# LCM32F037H6S8_024VDC_SCH_V1_0.net
KiCad netlist of a schematic drawn in Altium Designer
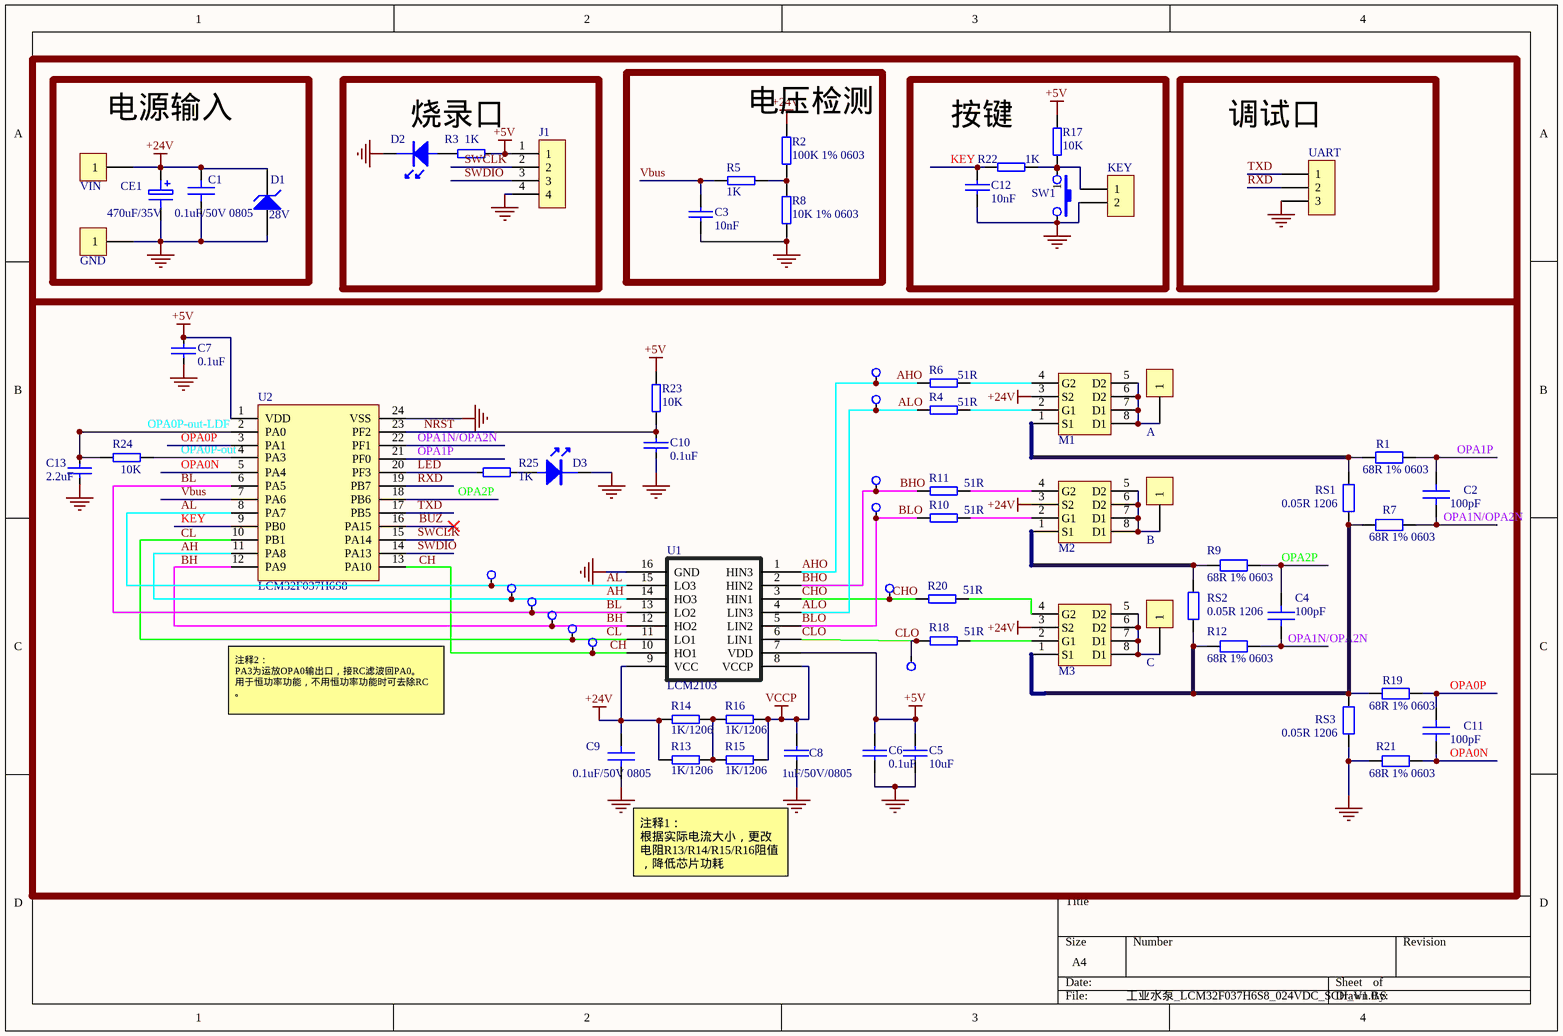
[diagram p0: 工业水泵_LCM32F037H6S8_024VDC_SCH_V1.0.SchDoc]

(export (version "E")
  (design (tool "Eeschema 10.0.6"))
  (components
    (comp (ref "A")
      (value "CON1")
      (footprint "CON-F1.5")
      (description "Connector")
      (libsource (lib "") (part "CON1_2"))
    )
    (comp (ref "B")
      (value "CON1")
      (footprint "CON-F1.5")
      (description "Connector")
      (libsource (lib "Miscellaneous Devices-HK") (part "CON1"))
    )
    (comp (ref "C")
      (value "CON1")
      (footprint "CON-F1.5")
      (description "Connector")
      (libsource (lib "") (part "CON1_2"))
    )
    (comp (ref "C1")
      (value "0.1uF/50V 0805")
      (footprint "C0805")
      (description "贴片电容")
      (libsource (lib "SCH-Tineco") (part "C-0603-104K50-X7R"))
    )
    (comp (ref "C2")
      (value "100pF")
      (footprint "C0603")
      (description "贴片电容")
      (libsource (lib "SCH-Tineco") (part "C-0603-104K50-X7R"))
    )
    (comp (ref "C3")
      (value "10nF")
      (footprint "C0603")
      (description "Capacitor")
      (libsource (lib "SunMaoZhi_SchematicLibrary") (part "CAP"))
    )
    (comp (ref "C4")
      (value "100pF")
      (footprint "C0603")
      (description "贴片电容")
      (libsource (lib "SCH-Tineco") (part "C-0603-104K50-X7R"))
    )
    (comp (ref "C5")
      (value "10uF")
      (footprint "C0805")
      (description "Capacitor")
      (libsource (lib "SunMaoZhi_SchematicLibrary") (part "CAP"))
    )
    (comp (ref "C6")
      (value "0.1uF")
      (footprint "C0603")
      (description "Capacitor")
      (libsource (lib "SunMaoZhi_SchematicLibrary") (part "CAP"))
    )
    (comp (ref "C7") (value "0.1uF") (footprint "C0603") (libsource (lib "MISCESCH") (part "CAP")))
    (comp (ref "C8")
      (value "1uF/50V/0805")
      (footprint "C0805")
      (description "Capacitor")
      (libsource (lib "SunMaoZhi_SchematicLibrary") (part "CAP"))
    )
    (comp (ref "C9")
      (value "0.1uF/50V 0805")
      (footprint "C0805X")
      (description "贴片电容")
      (libsource (lib "SCH-Tineco") (part "C-0603-104K50-X7R"))
    )
    (comp (ref "C10") (value "0.1uF") (footprint "C0603") (libsource (lib "MISCESCH") (part "CAP")))
    (comp (ref "C11")
      (value "100pF")
      (footprint "C0603")
      (description "贴片电容")
      (libsource (lib "SCH-Tineco") (part "C-0603-104K50-X7R"))
    )
    (comp (ref "C12")
      (value "10nF")
      (footprint "C0603")
      (description "Capacitor")
      (libsource (lib "SunMaoZhi_SchematicLibrary") (part "CAP"))
    )
    (comp (ref "C13") (value "2.2uF") (footprint "C0603") (libsource (lib "MISCESCH") (part "CAP")))
    (comp (ref "CE1")
      (value "470uF/35V")
      (footprint "C-DR10-5")
      (description "Electrolytic Capacitor")
      (libsource (lib "SunMaoZhi_SchematicLibrary") (part "CAP_ELECTRO"))
    )
    (comp (ref "D1")
      (value "28V")
      (footprint "SMB")
      (description "稳压管")
      (fields (field (name "PUBLISHER") "Altium Limited"))
      (libsource (lib "Miscellaneous Devices") (part "D Zener"))
    )
    (comp (ref "D2")
      (value "~")
      (footprint "0603-LED/H")
      (description "LED")
      (libsource (lib "MISCESCH") (part "LED"))
    )
    (comp (ref "D3")
      (value "~")
      (footprint "0603-LED/H")
      (description "LED")
      (libsource (lib "MISCESCH") (part "LED"))
    )
    (comp (ref "GND")
      (value "CON1")
      (footprint "CON-F1.5")
      (description "Connector")
      (libsource (lib "") (part "CON1_1"))
    )
    (comp (ref "J1") (value "CON4") (footprint "SIP4") (libsource (lib "*") (part "CON4")))
    (comp (ref "KEY")
      (value "CON2")
      (footprint "SIP2")
      (description "Connector")
      (libsource (lib "A1 Miscellaneous Devices") (part "CON2"))
    )
    (comp (ref "M1")
      (value "BPM0405CG")
      (footprint "SOP-8S")
      (libsource (lib "HK-SWSX-ZB001") (part "BPM0405CG"))
    )
    (comp (ref "M2")
      (value "BPM0405CG")
      (footprint "SOP-8S")
      (libsource (lib "HK-SWSX-ZB001") (part "BPM0405CG"))
    )
    (comp (ref "M3")
      (value "BPM0405CG")
      (footprint "SOP-8S")
      (libsource (lib "HK-SWSX-ZB001") (part "BPM0405CG"))
    )
    (comp (ref "R1")
      (value "68R 1% 0603")
      (footprint "R0603")
      (description "贴片电阻")
      (libsource (lib "SCH-Tineco") (part "R-0603-10K-J"))
    )
    (comp (ref "R2")
      (value "100K 1% 0603")
      (footprint "R0603")
      (libsource (lib "SunMaoZhi_SchematicLibrary") (part "RES"))
    )
    (comp (ref "R3") (value "1K") (footprint "R0603") (libsource (lib "MISCESCH") (part "RES")))
    (comp (ref "R4")
      (value "51R")
      (footprint "R0603")
      (libsource (lib "SunMaoZhi_SchematicLibrary") (part "RES"))
    )
    (comp (ref "R5")
      (value "1K")
      (footprint "R0603")
      (libsource (lib "SunMaoZhi_SchematicLibrary") (part "RES"))
    )
    (comp (ref "R6")
      (value "51R")
      (footprint "R0603")
      (libsource (lib "SunMaoZhi_SchematicLibrary") (part "RES"))
    )
    (comp (ref "R7")
      (value "68R 1% 0603")
      (footprint "R0603")
      (description "贴片电阻")
      (libsource (lib "SCH-Tineco") (part "R-0603-10K-J"))
    )
    (comp (ref "R8")
      (value "10K 1% 0603")
      (footprint "R0603")
      (libsource (lib "SunMaoZhi_SchematicLibrary") (part "RES"))
    )
    (comp (ref "R9")
      (value "68R 1% 0603")
      (footprint "R0603")
      (description "贴片电阻")
      (libsource (lib "SCH-Tineco") (part "R-0603-10K-J"))
    )
    (comp (ref "R10")
      (value "51R")
      (footprint "R0603")
      (libsource (lib "SunMaoZhi_SchematicLibrary") (part "RES"))
    )
    (comp (ref "R11")
      (value "51R")
      (footprint "R0603")
      (libsource (lib "SunMaoZhi_SchematicLibrary") (part "RES"))
    )
    (comp (ref "R12")
      (value "68R 1% 0603")
      (footprint "R0603")
      (description "贴片电阻")
      (libsource (lib "SCH-Tineco") (part "R-0603-10K-J"))
    )
    (comp (ref "R13")
      (value "1K/1206")
      (footprint "1206/X")
      (libsource (lib "SunMaoZhi_SchematicLibrary") (part "RES"))
    )
    (comp (ref "R14")
      (value "1K/1206")
      (footprint "1206/X")
      (libsource (lib "SunMaoZhi_SchematicLibrary") (part "RES"))
    )
    (comp (ref "R15")
      (value "1K/1206")
      (footprint "1206/X")
      (libsource (lib "SunMaoZhi_SchematicLibrary") (part "RES"))
    )
    (comp (ref "R16")
      (value "1K/1206")
      (footprint "1206/X")
      (libsource (lib "SunMaoZhi_SchematicLibrary") (part "RES"))
    )
    (comp (ref "R17")
      (value "10K")
      (footprint "R0603")
      (libsource (lib "SunMaoZhi_SchematicLibrary") (part "RES"))
    )
    (comp (ref "R18")
      (value "51R")
      (footprint "R0603")
      (libsource (lib "SunMaoZhi_SchematicLibrary") (part "RES"))
    )
    (comp (ref "R19")
      (value "68R 1% 0603")
      (footprint "R0603")
      (description "贴片电阻")
      (libsource (lib "SCH-Tineco") (part "R-0603-10K-J"))
    )
    (comp (ref "R20")
      (value "51R")
      (footprint "R0603")
      (libsource (lib "SunMaoZhi_SchematicLibrary") (part "RES"))
    )
    (comp (ref "R21")
      (value "68R 1% 0603")
      (footprint "R0603")
      (description "贴片电阻")
      (libsource (lib "SCH-Tineco") (part "R-0603-10K-J"))
    )
    (comp (ref "R22")
      (value "1K")
      (footprint "R0603")
      (libsource (lib "SunMaoZhi_SchematicLibrary") (part "RES"))
    )
    (comp (ref "R23")
      (value "10K")
      (footprint "R0603")
      (libsource (lib "SunMaoZhi_SchematicLibrary") (part "RES"))
    )
    (comp (ref "R24")
      (value "10K")
      (footprint "R0603")
      (libsource (lib "SunMaoZhi_SchematicLibrary") (part "RES"))
    )
    (comp (ref "R25") (value "1K") (footprint "R0603") (libsource (lib "MISCESCH") (part "RES")))
    (comp (ref "RS1")
      (value "0.05R 1206")
      (footprint "1206/X")
      (description "贴片电阻")
      (libsource (lib "") (part "R-0603-10K-J_1"))
    )
    (comp (ref "RS2")
      (value "0.05R 1206")
      (footprint "1206/X")
      (description "贴片电阻")
      (libsource (lib "") (part "R-0603-10K-J_1"))
    )
    (comp (ref "RS3")
      (value "0.05R 1206")
      (footprint "1206/X")
      (description "贴片电阻")
      (libsource (lib "SCH-Tineco") (part "R-0603-10K-J"))
    )
    (comp (ref "SW1") (value "SW-PB") (libsource (lib "A1 Miscellaneous Devices") (part "SW-PB")))
    (comp (ref "TP1")
      (value "TestPoint")
      (footprint "TP_1.0-A")
      (description "Testpoint")
      (libsource (lib "A1 Miscellaneous Devices") (part "TestPoint"))
    )
    (comp (ref "TP2")
      (value "TestPoint")
      (footprint "TP_1.0-A")
      (description "Testpoint")
      (libsource (lib "A1 Miscellaneous Devices") (part "TestPoint"))
    )
    (comp (ref "TP3")
      (value "TestPoint")
      (footprint "TP_1.0-A")
      (description "Testpoint")
      (libsource (lib "A1 Miscellaneous Devices") (part "TestPoint"))
    )
    (comp (ref "TP4")
      (value "TestPoint")
      (footprint "TP_1.0-A")
      (description "Testpoint")
      (libsource (lib "A1 Miscellaneous Devices") (part "TestPoint"))
    )
    (comp (ref "TP5")
      (value "TestPoint")
      (footprint "TP_1.0-A")
      (description "Testpoint")
      (libsource (lib "A1 Miscellaneous Devices") (part "TestPoint"))
    )
    (comp (ref "TP6")
      (value "TestPoint")
      (footprint "TP_1.0-A")
      (description "Testpoint")
      (libsource (lib "A1 Miscellaneous Devices") (part "TestPoint"))
    )
    (comp (ref "TP7")
      (value "TestPoint")
      (footprint "TP_1.0-A")
      (description "Testpoint")
      (libsource (lib "A1 Miscellaneous Devices") (part "TestPoint"))
    )
    (comp (ref "TP8")
      (value "TestPoint")
      (footprint "TP_1.0-A")
      (description "Testpoint")
      (libsource (lib "A1 Miscellaneous Devices") (part "TestPoint"))
    )
    (comp (ref "TP9")
      (value "TestPoint")
      (footprint "TP_1.0-A")
      (description "Testpoint")
      (libsource (lib "A1 Miscellaneous Devices") (part "TestPoint"))
    )
    (comp (ref "TP10")
      (value "TestPoint")
      (footprint "TP_1.0-A")
      (description "Testpoint")
      (libsource (lib "A1 Miscellaneous Devices") (part "TestPoint"))
    )
    (comp (ref "TP11")
      (value "TestPoint")
      (footprint "TP_1.0-A")
      (description "Testpoint")
      (libsource (lib "A1 Miscellaneous Devices") (part "TestPoint"))
    )
    (comp (ref "TP12")
      (value "TestPoint")
      (footprint "TP_1.0-A")
      (description "Testpoint")
      (libsource (lib "A1 Miscellaneous Devices") (part "TestPoint"))
    )
    (comp (ref "U1") (value "LCM2103") (footprint "SOP16") (libsource (lib "*") (part "MX8324")))
    (comp (ref "U2") (value "LCM32F037H6S8") (footprint "SSOP24-H") (libsource (lib "fan") (part "LM32")))
    (comp (ref "UART")
      (value "CON3")
      (footprint "SIP3")
      (description "Connector")
      (libsource (lib "A1 Miscellaneous Devices") (part "CON3"))
    )
    (comp (ref "VIN")
      (value "CON1")
      (footprint "CON-F1.5")
      (description "Connector")
      (libsource (lib "") (part "CON1_1"))
    )
  )
  (nets
    (net (code "1") (name "+5V") (class "Default")
      (node (ref "C5") (pin "2") (pinfunction "2_2") (pintype "passive"))
      (node (ref "C6") (pin "2") (pinfunction "2_2") (pintype "passive"))
      (node (ref "C7") (pin "1") (pintype "passive"))
      (node (ref "J1") (pin "1") (pinfunction "1_1") (pintype "passive"))
      (node (ref "R17") (pin "1") (pinfunction "1_1") (pintype "passive"))
      (node (ref "R23") (pin "1") (pinfunction "1_1") (pintype "passive"))
      (node (ref "R3") (pin "2") (pintype "passive"))
      (node (ref "U1") (pin "7") (pinfunction "VDD_7") (pintype "passive"))
      (node (ref "U2") (pin "1") (pinfunction "VDD_1") (pintype "passive"))
    )
    (net (code "2") (name "+24V") (class "Default")
      (node (ref "C1") (pin "1") (pinfunction "1_1") (pintype "passive"))
      (node (ref "C9") (pin "1") (pinfunction "1_1") (pintype "passive"))
      (node (ref "CE1") (pin "1") (pinfunction "1_1") (pintype "passive"))
      (node (ref "D1") (pin "2") (pinfunction "K_2") (pintype "passive"))
      (node (ref "M1") (pin "3") (pinfunction "S2_3") (pintype "passive"))
      (node (ref "M2") (pin "3") (pinfunction "S2_3") (pintype "passive"))
      (node (ref "M3") (pin "3") (pinfunction "S2_3") (pintype "passive"))
      (node (ref "R13") (pin "2") (pinfunction "2_2") (pintype "passive"))
      (node (ref "R14") (pin "2") (pinfunction "2_2") (pintype "passive"))
      (node (ref "R2") (pin "1") (pinfunction "1_1") (pintype "passive"))
      (node (ref "U1") (pin "9") (pinfunction "VCC_9") (pintype "passive"))
      (node (ref "VIN") (pin "1") (pinfunction "1_1") (pintype "passive"))
    )
    (net (code "3") (name "/AH") (class "Default")
      (node (ref "TP8") (pin "1") (pinfunction "1_1") (pintype "passive"))
      (node (ref "U1") (pin "14") (pinfunction "HO3_14") (pintype "passive"))
      (node (ref "U2") (pin "11") (pinfunction "PA8_11") (pintype "passive"))
    )
    (net (code "4") (name "/AHO") (class "Default")
      (node (ref "R6") (pin "1") (pinfunction "1_1") (pintype "passive"))
      (node (ref "TP1") (pin "1") (pinfunction "1_1") (pintype "passive"))
      (node (ref "U1") (pin "1") (pinfunction "HIN3_1") (pintype "passive"))
    )
    (net (code "5") (name "/AL") (class "Default")
      (node (ref "TP7") (pin "1") (pinfunction "1_1") (pintype "passive"))
      (node (ref "U1") (pin "15") (pinfunction "LO3_15") (pintype "passive"))
      (node (ref "U2") (pin "8") (pinfunction "PA7_8") (pintype "passive"))
    )
    (net (code "6") (name "/ALO") (class "Default")
      (node (ref "R4") (pin "1") (pinfunction "1_1") (pintype "passive"))
      (node (ref "TP2") (pin "1") (pinfunction "1_1") (pintype "passive"))
      (node (ref "U1") (pin "4") (pinfunction "LIN3_4") (pintype "passive"))
    )
    (net (code "7") (name "/BH") (class "Default")
      (node (ref "TP10") (pin "1") (pinfunction "1_1") (pintype "passive"))
      (node (ref "U1") (pin "12") (pinfunction "HO2_12") (pintype "passive"))
      (node (ref "U2") (pin "12") (pinfunction "PA9_12") (pintype "passive"))
    )
    (net (code "8") (name "/BHO") (class "Default")
      (node (ref "R11") (pin "1") (pinfunction "1_1") (pintype "passive"))
      (node (ref "TP3") (pin "1") (pinfunction "1_1") (pintype "passive"))
      (node (ref "U1") (pin "2") (pinfunction "HIN2_2") (pintype "passive"))
    )
    (net (code "9") (name "/BL") (class "Default")
      (node (ref "TP9") (pin "1") (pinfunction "1_1") (pintype "passive"))
      (node (ref "U1") (pin "13") (pinfunction "LO2_13") (pintype "passive"))
      (node (ref "U2") (pin "6") (pinfunction "PA5_6") (pintype "passive"))
    )
    (net (code "10") (name "/BLO") (class "Default")
      (node (ref "R10") (pin "1") (pinfunction "1_1") (pintype "passive"))
      (node (ref "TP4") (pin "1") (pinfunction "1_1") (pintype "passive"))
      (node (ref "U1") (pin "5") (pinfunction "LIN2_5") (pintype "passive"))
    )
    (net (code "11") (name "/BUZ") (class "Default")
      (node (ref "U2") (pin "16") (pinfunction "PA15_16") (pintype "passive+no_connect"))
    )
    (net (code "12") (name "/CH") (class "Default")
      (node (ref "TP12") (pin "1") (pinfunction "1_1") (pintype "passive"))
      (node (ref "U1") (pin "10") (pinfunction "HO1_10") (pintype "passive"))
      (node (ref "U2") (pin "13") (pinfunction "PA10_13") (pintype "passive"))
    )
    (net (code "13") (name "/CHO") (class "Default")
      (node (ref "R20") (pin "1") (pinfunction "1_1") (pintype "passive"))
      (node (ref "TP5") (pin "1") (pinfunction "1_1") (pintype "passive"))
      (node (ref "U1") (pin "3") (pinfunction "HIN1_3") (pintype "passive"))
    )
    (net (code "14") (name "/CL") (class "Default")
      (node (ref "TP11") (pin "1") (pinfunction "1_1") (pintype "passive"))
      (node (ref "U1") (pin "11") (pinfunction "LO1_11") (pintype "passive"))
      (node (ref "U2") (pin "10") (pinfunction "PB1_10") (pintype "passive"))
    )
    (net (code "15") (name "/CLO") (class "Default")
      (node (ref "R18") (pin "1") (pinfunction "1_1") (pintype "passive"))
      (node (ref "TP6") (pin "1") (pinfunction "1_1") (pintype "passive"))
      (node (ref "U1") (pin "6") (pinfunction "LIN1_6") (pintype "passive"))
    )
    (net (code "16") (name "/KEY") (class "Default")
      (node (ref "C12") (pin "1") (pinfunction "1_1") (pintype "passive"))
      (node (ref "R22") (pin "1") (pinfunction "1_1") (pintype "passive"))
      (node (ref "U2") (pin "9") (pinfunction "PB0_9") (pintype "passive"))
    )
    (net (code "17") (name "/LED") (class "Default")
      (node (ref "R25") (pin "2") (pintype "passive"))
      (node (ref "U2") (pin "20") (pinfunction "PF3_20") (pintype "passive"))
    )
    (net (code "18") (name "/NRST") (class "Default")
      (node (ref "C10") (pin "1") (pintype "passive"))
      (node (ref "R23") (pin "2") (pinfunction "2_2") (pintype "passive"))
      (node (ref "U2") (pin "23") (pinfunction "PF2_23") (pintype "passive"))
    )
    (net (code "19") (name "/OPA0N") (class "Default")
      (node (ref "C11") (pin "1") (pinfunction "1_1") (pintype "passive"))
      (node (ref "R21") (pin "1") (pinfunction "1_1") (pintype "passive"))
      (node (ref "U2") (pin "5") (pinfunction "PA4_5") (pintype "passive"))
    )
    (net (code "20") (name "/OPA0P") (class "Default")
      (node (ref "C11") (pin "2") (pinfunction "2_2") (pintype "passive"))
      (node (ref "R19") (pin "1") (pinfunction "1_1") (pintype "passive"))
      (node (ref "U2") (pin "3") (pinfunction "PA1_3") (pintype "passive"))
    )
    (net (code "21") (name "/OPA0P-out") (class "Default")
      (node (ref "R24") (pin "1") (pinfunction "1_1") (pintype "passive"))
      (node (ref "U2") (pin "4") (pinfunction "PA3_4") (pintype "passive"))
    )
    (net (code "22") (name "/OPA0P-out-LDF") (class "Default")
      (node (ref "C13") (pin "1") (pintype "passive"))
      (node (ref "R24") (pin "2") (pinfunction "2_2") (pintype "passive"))
      (node (ref "U2") (pin "2") (pinfunction "PA0_2") (pintype "passive"))
    )
    (net (code "23") (name "/OPA1N{slash}OPA2N") (class "Default")
      (node (ref "C2") (pin "1") (pinfunction "1_1") (pintype "passive"))
      (node (ref "C4") (pin "1") (pinfunction "1_1") (pintype "passive"))
      (node (ref "R12") (pin "1") (pinfunction "1_1") (pintype "passive"))
      (node (ref "R7") (pin "1") (pinfunction "1_1") (pintype "passive"))
      (node (ref "U2") (pin "22") (pinfunction "PF1_22") (pintype "passive"))
    )
    (net (code "24") (name "/OPA1P") (class "Default")
      (node (ref "C2") (pin "2") (pinfunction "2_2") (pintype "passive"))
      (node (ref "R1") (pin "1") (pinfunction "1_1") (pintype "passive"))
      (node (ref "U2") (pin "21") (pinfunction "PF0_21") (pintype "passive"))
    )
    (net (code "25") (name "/OPA2P") (class "Default")
      (node (ref "C4") (pin "2") (pinfunction "2_2") (pintype "passive"))
      (node (ref "R9") (pin "1") (pinfunction "1_1") (pintype "passive"))
      (node (ref "U2") (pin "18") (pinfunction "PB6_18") (pintype "passive"))
    )
    (net (code "26") (name "/RXD") (class "Default")
      (node (ref "U2") (pin "19") (pinfunction "PB7_19") (pintype "passive"))
      (node (ref "UART") (pin "2") (pinfunction "2_2") (pintype "passive"))
    )
    (net (code "27") (name "/SWCLK") (class "Default")
      (node (ref "J1") (pin "2") (pinfunction "2_2") (pintype "passive"))
      (node (ref "U2") (pin "15") (pinfunction "PA14_15") (pintype "passive"))
    )
    (net (code "28") (name "/SWDIO") (class "Default")
      (node (ref "J1") (pin "3") (pinfunction "3_3") (pintype "passive"))
      (node (ref "U2") (pin "14") (pinfunction "PA13_14") (pintype "passive"))
    )
    (net (code "29") (name "/TXD") (class "Default")
      (node (ref "U2") (pin "17") (pinfunction "PB5_17") (pintype "passive"))
      (node (ref "UART") (pin "1") (pinfunction "1_1") (pintype "passive"))
    )
    (net (code "30") (name "/Vbus") (class "Default")
      (node (ref "C3") (pin "1") (pinfunction "1_1") (pintype "passive"))
      (node (ref "R5") (pin "2") (pinfunction "2_2") (pintype "passive"))
      (node (ref "U2") (pin "7") (pinfunction "PA6_7") (pintype "passive"))
    )
    (net (code "31") (name "GND") (class "Default")
      (node (ref "C1") (pin "2") (pinfunction "2_2") (pintype "passive"))
      (node (ref "C10") (pin "2") (pintype "passive"))
      (node (ref "C12") (pin "2") (pinfunction "2_2") (pintype "passive"))
      (node (ref "C13") (pin "2") (pintype "passive"))
      (node (ref "C3") (pin "2") (pinfunction "2_2") (pintype "passive"))
      (node (ref "C5") (pin "1") (pinfunction "1_1") (pintype "passive"))
      (node (ref "C6") (pin "1") (pinfunction "1_1") (pintype "passive"))
      (node (ref "C7") (pin "2") (pintype "passive"))
      (node (ref "C8") (pin "1") (pinfunction "1_1") (pintype "passive"))
      (node (ref "C9") (pin "2") (pinfunction "2_2") (pintype "passive"))
      (node (ref "CE1") (pin "2") (pinfunction "2_2") (pintype "passive"))
      (node (ref "D1") (pin "1") (pinfunction "A_1") (pintype "passive"))
      (node (ref "D2") (pin "1") (pinfunction "1_1") (pintype "passive"))
      (node (ref "D3") (pin "1") (pinfunction "1_1") (pintype "passive"))
      (node (ref "GND") (pin "1") (pinfunction "1_1") (pintype "passive"))
      (node (ref "J1") (pin "4") (pinfunction "4_4") (pintype "passive"))
      (node (ref "KEY") (pin "2") (pinfunction "2_2") (pintype "passive"))
      (node (ref "R21") (pin "2") (pinfunction "2_2") (pintype "passive"))
      (node (ref "R8") (pin "2") (pinfunction "2_2") (pintype "passive"))
      (node (ref "RS3") (pin "2") (pinfunction "2_2") (pintype "passive"))
      (node (ref "SW1") (pin "2") (pinfunction "2_2") (pintype "passive"))
      (node (ref "U1") (pin "16") (pinfunction "GND_16") (pintype "passive"))
      (node (ref "U2") (pin "24") (pinfunction "VSS_24") (pintype "passive"))
      (node (ref "UART") (pin "3") (pinfunction "3_3") (pintype "passive"))
    )
    (net (code "32") (name "Net-(A-Pad1)") (class "Default")
      (node (ref "A") (pin "1") (pinfunction "1_1") (pintype "passive"))
      (node (ref "M1") (pin "5") (pinfunction "D2_5") (pintype "passive"))
      (node (ref "M1") (pin "6") (pinfunction "D2_6") (pintype "passive"))
      (node (ref "M1") (pin "7") (pinfunction "D1_7") (pintype "passive"))
      (node (ref "M1") (pin "8") (pinfunction "D1_8") (pintype "passive"))
    )
    (net (code "33") (name "Net-(B-Pad1)") (class "Default")
      (node (ref "B") (pin "1") (pinfunction "1_1") (pintype "passive"))
      (node (ref "M2") (pin "5") (pinfunction "D2_5") (pintype "passive"))
      (node (ref "M2") (pin "6") (pinfunction "D2_6") (pintype "passive"))
      (node (ref "M2") (pin "7") (pinfunction "D1_7") (pintype "passive"))
      (node (ref "M2") (pin "8") (pinfunction "D1_8") (pintype "passive"))
    )
    (net (code "34") (name "Net-(C-Pad1)") (class "Default")
      (node (ref "C") (pin "1") (pinfunction "1_1") (pintype "passive"))
      (node (ref "M3") (pin "5") (pinfunction "D2_5") (pintype "passive"))
      (node (ref "M3") (pin "6") (pinfunction "D2_6") (pintype "passive"))
      (node (ref "M3") (pin "7") (pinfunction "D1_7") (pintype "passive"))
      (node (ref "M3") (pin "8") (pinfunction "D1_8") (pintype "passive"))
    )
    (net (code "35") (name "Net-(D2-Pad2)") (class "Default")
      (node (ref "D2") (pin "2") (pinfunction "2_2") (pintype "passive"))
      (node (ref "R3") (pin "1") (pintype "passive"))
    )
    (net (code "36") (name "Net-(D3-Pad2)") (class "Default")
      (node (ref "D3") (pin "2") (pinfunction "2_2") (pintype "passive"))
      (node (ref "R25") (pin "1") (pintype "passive"))
    )
    (net (code "37") (name "Net-(KEY-Pad1)") (class "Default")
      (node (ref "KEY") (pin "1") (pinfunction "1_1") (pintype "passive"))
      (node (ref "R17") (pin "2") (pinfunction "2_2") (pintype "passive"))
      (node (ref "R22") (pin "2") (pinfunction "2_2") (pintype "passive"))
      (node (ref "SW1") (pin "1") (pinfunction "1_1") (pintype "passive"))
    )
    (net (code "38") (name "Net-(M1-G1)") (class "Default")
      (node (ref "M1") (pin "2") (pinfunction "G1_2") (pintype "passive"))
      (node (ref "R4") (pin "2") (pinfunction "2_2") (pintype "passive"))
    )
    (net (code "39") (name "Net-(M1-G2)") (class "Default")
      (node (ref "M1") (pin "4") (pinfunction "G2_4") (pintype "passive"))
      (node (ref "R6") (pin "2") (pinfunction "2_2") (pintype "passive"))
    )
    (net (code "40") (name "Net-(M1-S1)") (class "Default")
      (node (ref "M1") (pin "1") (pinfunction "S1_1") (pintype "passive"))
      (node (ref "R1") (pin "2") (pinfunction "2_2") (pintype "passive"))
      (node (ref "RS1") (pin "1") (pinfunction "1_1") (pintype "passive"))
    )
    (net (code "41") (name "Net-(M2-G1)") (class "Default")
      (node (ref "M2") (pin "2") (pinfunction "G1_2") (pintype "passive"))
      (node (ref "R10") (pin "2") (pinfunction "2_2") (pintype "passive"))
    )
    (net (code "42") (name "Net-(M2-G2)") (class "Default")
      (node (ref "M2") (pin "4") (pinfunction "G2_4") (pintype "passive"))
      (node (ref "R11") (pin "2") (pinfunction "2_2") (pintype "passive"))
    )
    (net (code "43") (name "Net-(M2-S1)") (class "Default")
      (node (ref "M2") (pin "1") (pinfunction "S1_1") (pintype "passive"))
      (node (ref "R9") (pin "2") (pinfunction "2_2") (pintype "passive"))
      (node (ref "RS2") (pin "1") (pinfunction "1_1") (pintype "passive"))
    )
    (net (code "44") (name "Net-(M3-G1)") (class "Default")
      (node (ref "M3") (pin "2") (pinfunction "G1_2") (pintype "passive"))
      (node (ref "R18") (pin "2") (pinfunction "2_2") (pintype "passive"))
    )
    (net (code "45") (name "Net-(M3-G2)") (class "Default")
      (node (ref "M3") (pin "4") (pinfunction "G2_4") (pintype "passive"))
      (node (ref "R20") (pin "2") (pinfunction "2_2") (pintype "passive"))
    )
    (net (code "46") (name "Net-(M3-S1)") (class "Default")
      (node (ref "M3") (pin "1") (pinfunction "S1_1") (pintype "passive"))
      (node (ref "R12") (pin "2") (pinfunction "2_2") (pintype "passive"))
      (node (ref "R19") (pin "2") (pinfunction "2_2") (pintype "passive"))
      (node (ref "R7") (pin "2") (pinfunction "2_2") (pintype "passive"))
      (node (ref "RS1") (pin "2") (pinfunction "2_2") (pintype "passive"))
      (node (ref "RS2") (pin "2") (pinfunction "2_2") (pintype "passive"))
      (node (ref "RS3") (pin "1") (pinfunction "1_1") (pintype "passive"))
    )
    (net (code "47") (name "Net-(R2-Pad2)") (class "Default")
      (node (ref "R2") (pin "2") (pinfunction "2_2") (pintype "passive"))
      (node (ref "R5") (pin "1") (pinfunction "1_1") (pintype "passive"))
      (node (ref "R8") (pin "1") (pinfunction "1_1") (pintype "passive"))
    )
    (net (code "48") (name "Net-(R13-Pad1)") (class "Default")
      (node (ref "R13") (pin "1") (pinfunction "1_1") (pintype "passive"))
      (node (ref "R14") (pin "1") (pinfunction "1_1") (pintype "passive"))
      (node (ref "R15") (pin "2") (pinfunction "2_2") (pintype "passive"))
      (node (ref "R16") (pin "2") (pinfunction "2_2") (pintype "passive"))
    )
    (net (code "49") (name "VCCP") (class "Default")
      (node (ref "C8") (pin "2") (pinfunction "2_2") (pintype "passive"))
      (node (ref "R15") (pin "1") (pinfunction "1_1") (pintype "passive"))
      (node (ref "R16") (pin "1") (pinfunction "1_1") (pintype "passive"))
      (node (ref "U1") (pin "8") (pinfunction "VCCP_8") (pintype "passive"))
    )
  )
)
